# dwarfid.net
KiCad netlist of a schematic drawn in EAGLE
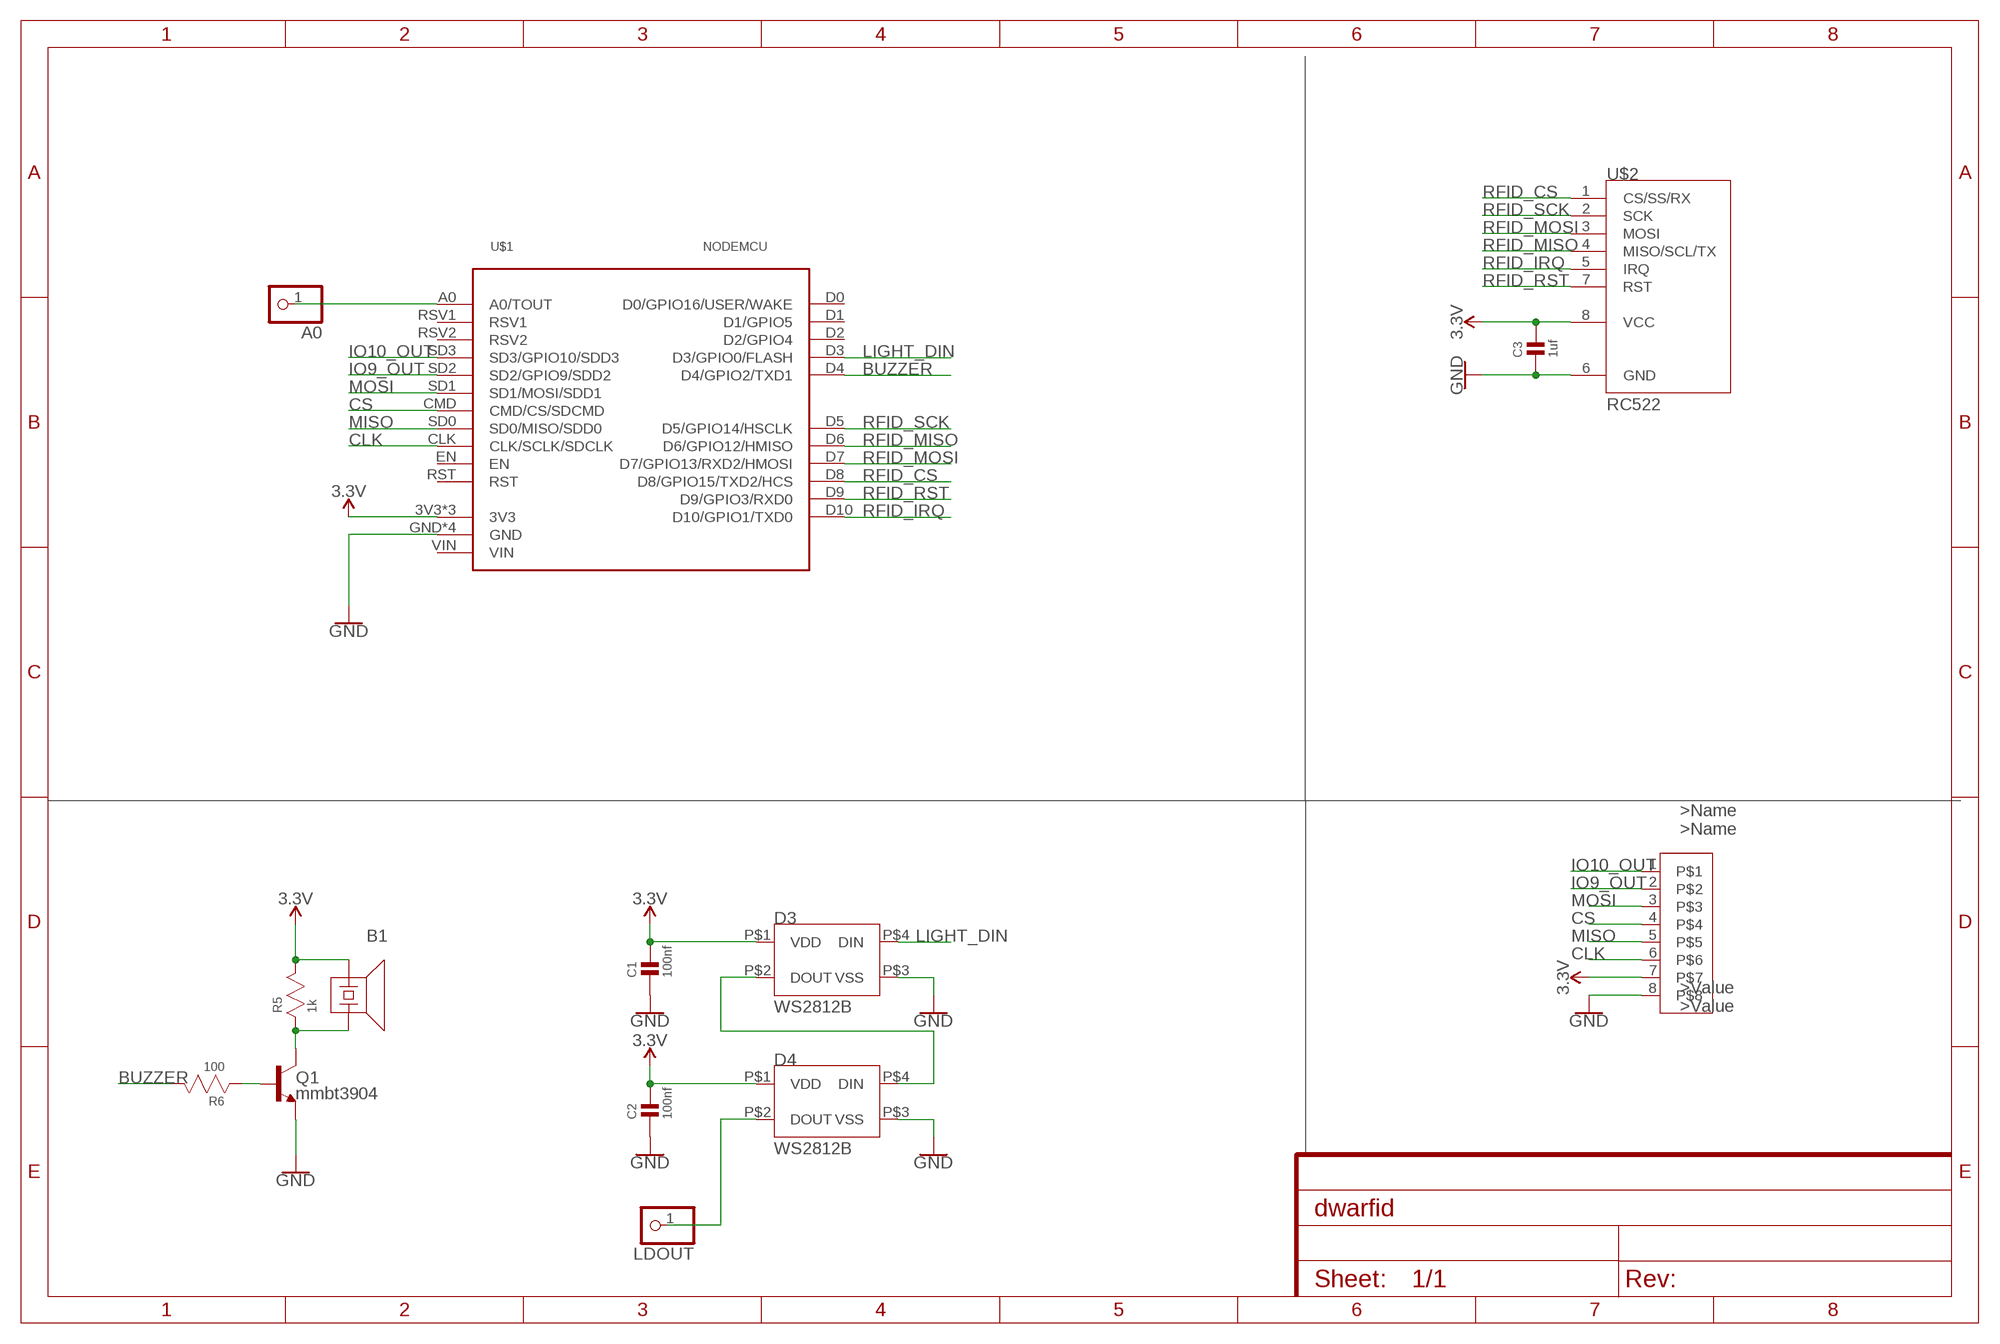
[diagram p0: schematic, sheet 1]

(export (version "E")
  (design (tool "Eeschema 10.0.6"))
  (components
    (comp (ref "A0")
      (value "PINHD-1X1")
      (footprint "eagle-import:1X01")
      (libsource (lib "eagle-import") (part "PINHD-1X1"))
    )
    (comp (ref "B1")
      (value "PS1720P02_PIEZO_BUZZER")
      (footprint "eagle-import:PS1720P02_PIEZO")
      (libsource (lib "eagle-import") (part "PS1720P02_PIEZO_BUZZER"))
    )
    (comp (ref "C1")
      (value "100nf")
      (footprint "eagle-import:PASSIVE_0603")
      (libsource (lib "eagle-import") (part "CAP_0603"))
    )
    (comp (ref "C2")
      (value "100nf")
      (footprint "eagle-import:PASSIVE_0603")
      (libsource (lib "eagle-import") (part "CAP_0603"))
    )
    (comp (ref "C3")
      (value "1uf")
      (footprint "eagle-import:PASSIVE_0603")
      (libsource (lib "eagle-import") (part "CAP_0603"))
    )
    (comp (ref "D3")
      (value "WS2812B")
      (footprint "eagle-import:WS2812B")
      (libsource (lib "eagle-import") (part "WS2812B"))
    )
    (comp (ref "D4")
      (value "WS2812B")
      (footprint "eagle-import:WS2812B")
      (libsource (lib "eagle-import") (part "WS2812B"))
    )
    (comp (ref "LDOUT")
      (value "PINHD-1X1")
      (footprint "eagle-import:1X01")
      (libsource (lib "eagle-import") (part "PINHD-1X1"))
    )
    (comp (ref "Q1")
      (value "mmbt3904")
      (footprint "eagle-import:SOT23-3")
      (libsource (lib "eagle-import") (part "TRANS_NPN-MMBT2222AL"))
    )
    (comp (ref "R5")
      (value "1k")
      (footprint "eagle-import:PASSIVE_0603")
      (libsource (lib "eagle-import") (part "RES_0603"))
    )
    (comp (ref "R6")
      (value "100")
      (footprint "eagle-import:PASSIVE_0603")
      (libsource (lib "eagle-import") (part "RES_0603"))
    )
    (comp (ref "U$1")
      (value "NODEMCU")
      (footprint "eagle-import:NODEMCU")
      (libsource (lib "eagle-import") (part "NODEMCU"))
    )
    (comp (ref "U$2")
      (value "RC522")
      (footprint "eagle-import:RC522")
      (libsource (lib "eagle-import") (part "RC522"))
    )
    (comp (ref "U$3")
      (value "JST8_2MM_RIGHTANGLE")
      (footprint "eagle-import:JST_2MM_8POS")
      (libsource (lib "eagle-import") (part "JST8_2MM_RIGHTANGLE"))
    )
  )
  (nets
    (net (code "1") (name "/BUZZER") (class "Default")
      (node (ref "R6") (pin "P$2") (pinfunction "P$2_P$2") (pintype "bidirectional"))
      (node (ref "U$1") (pin "D4") (pinfunction "D4/GPIO2/TXD1_D4") (pintype "bidirectional"))
    )
    (net (code "2") (name "/CLK") (class "Default")
      (node (ref "U$1") (pin "CLK") (pinfunction "CLK/SCLK/SDCLK_CLK") (pintype "bidirectional"))
      (node (ref "U$3") (pin "6") (pinfunction "P$6_6") (pintype "bidirectional"))
    )
    (net (code "3") (name "/CS") (class "Default")
      (node (ref "U$1") (pin "CMD") (pinfunction "CMD/CS/SDCMD_CMD") (pintype "bidirectional"))
      (node (ref "U$3") (pin "4") (pinfunction "P$4_4") (pintype "bidirectional"))
    )
    (net (code "4") (name "/IO9_OUT") (class "Default")
      (node (ref "U$1") (pin "SD2") (pinfunction "SD2/GPIO9/SDD2_SD2") (pintype "bidirectional"))
      (node (ref "U$3") (pin "2") (pinfunction "P$2_2") (pintype "bidirectional"))
    )
    (net (code "5") (name "/IO10_OUT") (class "Default")
      (node (ref "U$1") (pin "SD3") (pinfunction "SD3/GPIO10/SDD3_SD3") (pintype "bidirectional"))
      (node (ref "U$3") (pin "1") (pinfunction "P$1_1") (pintype "bidirectional"))
    )
    (net (code "6") (name "/LIGHT_DIN") (class "Default")
      (node (ref "D3") (pin "P$4") (pinfunction "DIN_P$4") (pintype "bidirectional"))
      (node (ref "U$1") (pin "D3") (pinfunction "D3/GPIO0/FLASH_D3") (pintype "bidirectional"))
    )
    (net (code "7") (name "/MISO") (class "Default")
      (node (ref "U$1") (pin "SD0") (pinfunction "SD0/MISO/SDD0_SD0") (pintype "bidirectional"))
      (node (ref "U$3") (pin "5") (pinfunction "P$5_5") (pintype "bidirectional"))
    )
    (net (code "8") (name "/MOSI") (class "Default")
      (node (ref "U$1") (pin "SD1") (pinfunction "SD1/MOSI/SDD1_SD1") (pintype "bidirectional"))
      (node (ref "U$3") (pin "3") (pinfunction "P$3_3") (pintype "bidirectional"))
    )
    (net (code "9") (name "/RFID_CS") (class "Default")
      (node (ref "U$1") (pin "D8") (pinfunction "D8/GPIO15/TXD2/HCS_D8") (pintype "bidirectional"))
      (node (ref "U$2") (pin "1") (pinfunction "CS/SS/RX_1") (pintype "bidirectional"))
    )
    (net (code "10") (name "/RFID_IRQ") (class "Default")
      (node (ref "U$1") (pin "D10") (pinfunction "D10/GPIO1/TXD0_D10") (pintype "bidirectional"))
      (node (ref "U$2") (pin "5") (pinfunction "IRQ_5") (pintype "bidirectional"))
    )
    (net (code "11") (name "/RFID_MISO") (class "Default")
      (node (ref "U$1") (pin "D6") (pinfunction "D6/GPIO12/HMISO_D6") (pintype "bidirectional"))
      (node (ref "U$2") (pin "4") (pinfunction "MISO/SCL/TX_4") (pintype "bidirectional"))
    )
    (net (code "12") (name "/RFID_MOSI") (class "Default")
      (node (ref "U$1") (pin "D7") (pinfunction "D7/GPIO13/RXD2/HMOSI_D7") (pintype "bidirectional"))
      (node (ref "U$2") (pin "3") (pinfunction "MOSI_3") (pintype "bidirectional"))
    )
    (net (code "13") (name "/RFID_RST") (class "Default")
      (node (ref "U$1") (pin "D9") (pinfunction "D9/GPIO3/RXD0_D9") (pintype "bidirectional"))
      (node (ref "U$2") (pin "7") (pinfunction "RST_7") (pintype "bidirectional"))
    )
    (net (code "14") (name "/RFID_SCK") (class "Default")
      (node (ref "U$1") (pin "D5") (pinfunction "D5/GPIO14/HSCLK_D5") (pintype "bidirectional"))
      (node (ref "U$2") (pin "2") (pinfunction "SCK_2") (pintype "bidirectional"))
    )
    (net (code "15") (name "3.3V") (class "Default")
      (node (ref "B1") (pin "P$1") (pinfunction "P$1_P$1") (pintype "bidirectional"))
      (node (ref "C1") (pin "P$2") (pinfunction "P$2_P$2") (pintype "bidirectional"))
      (node (ref "C2") (pin "P$2") (pinfunction "P$2_P$2") (pintype "bidirectional"))
      (node (ref "C3") (pin "P$2") (pinfunction "P$2_P$2") (pintype "bidirectional"))
      (node (ref "D3") (pin "P$1") (pinfunction "VDD_P$1") (pintype "bidirectional"))
      (node (ref "D4") (pin "P$1") (pinfunction "VDD_P$1") (pintype "bidirectional"))
      (node (ref "R5") (pin "P$2") (pinfunction "P$2_P$2") (pintype "bidirectional"))
      (node (ref "U$1") (pin "3V3") (pinfunction "3V3_3V3") (pintype "bidirectional"))
      (node (ref "U$1") (pin "3V3_2") (pinfunction "3V3_3V3_2") (pintype "bidirectional"))
      (node (ref "U$1") (pin "3V3_3") (pinfunction "3V3_3V3_3") (pintype "bidirectional"))
      (node (ref "U$2") (pin "8") (pinfunction "VCC_8") (pintype "bidirectional"))
      (node (ref "U$3") (pin "7") (pinfunction "P$7_7") (pintype "bidirectional"))
    )
    (net (code "16") (name "GND") (class "Default")
      (node (ref "C1") (pin "P$1") (pinfunction "P$1_P$1") (pintype "bidirectional"))
      (node (ref "C2") (pin "P$1") (pinfunction "P$1_P$1") (pintype "bidirectional"))
      (node (ref "C3") (pin "P$1") (pinfunction "P$1_P$1") (pintype "bidirectional"))
      (node (ref "D3") (pin "P$3") (pinfunction "VSS_P$3") (pintype "bidirectional"))
      (node (ref "D4") (pin "P$3") (pinfunction "VSS_P$3") (pintype "bidirectional"))
      (node (ref "Q1") (pin "2") (pinfunction "E_2") (pintype "passive"))
      (node (ref "U$1") (pin "GND") (pinfunction "GND_GND") (pintype "bidirectional"))
      (node (ref "U$1") (pin "GND2") (pinfunction "GND_GND2") (pintype "bidirectional"))
      (node (ref "U$1") (pin "GND3") (pinfunction "GND_GND3") (pintype "bidirectional"))
      (node (ref "U$1") (pin "GND4") (pinfunction "GND_GND4") (pintype "bidirectional"))
      (node (ref "U$2") (pin "6") (pinfunction "GND_6") (pintype "bidirectional"))
      (node (ref "U$3") (pin "8") (pinfunction "P$8_8") (pintype "bidirectional"))
    )
    (net (code "17") (name "Net-(D3-DOUT)") (class "Default")
      (node (ref "D3") (pin "P$2") (pinfunction "DOUT_P$2") (pintype "bidirectional"))
      (node (ref "D4") (pin "P$4") (pinfunction "DIN_P$4") (pintype "bidirectional"))
    )
    (net (code "18") (name "Net-(D4-DOUT)") (class "Default")
      (node (ref "D4") (pin "P$2") (pinfunction "DOUT_P$2") (pintype "bidirectional"))
      (node (ref "LDOUT") (pin "1") (pinfunction "1_1") (pintype "passive"))
    )
    (net (code "19") (name "Net-(Q1-B)") (class "Default")
      (node (ref "Q1") (pin "1") (pinfunction "B_1") (pintype "passive"))
      (node (ref "R6") (pin "P$1") (pinfunction "P$1_P$1") (pintype "bidirectional"))
    )
    (net (code "20") (name "Net-(Q1-C)") (class "Default")
      (node (ref "B1") (pin "P$2") (pinfunction "P$2_P$2") (pintype "bidirectional"))
      (node (ref "Q1") (pin "3") (pinfunction "C_3") (pintype "passive"))
      (node (ref "R5") (pin "P$1") (pinfunction "P$1_P$1") (pintype "bidirectional"))
    )
    (net (code "21") (name "Net-(U$1-A0{slash}TOUT)") (class "Default")
      (node (ref "A0") (pin "1") (pinfunction "1_1") (pintype "passive"))
      (node (ref "U$1") (pin "A0") (pinfunction "A0/TOUT_A0") (pintype "bidirectional"))
    )
    (net (code "22") (name "unconnected-(U$1-D0{slash}GPIO16{slash}USER{slash}WAKE-PadD0)") (class "Default")
      (node (ref "U$1") (pin "D0") (pinfunction "D0/GPIO16/USER/WAKE_D0") (pintype "bidirectional"))
    )
    (net (code "23") (name "unconnected-(U$1-D1{slash}GPIO5-PadD1)") (class "Default")
      (node (ref "U$1") (pin "D1") (pinfunction "D1/GPIO5_D1") (pintype "bidirectional"))
    )
    (net (code "24") (name "unconnected-(U$1-D2{slash}GPIO4-PadD2)") (class "Default")
      (node (ref "U$1") (pin "D2") (pinfunction "D2/GPIO4_D2") (pintype "bidirectional"))
    )
    (net (code "25") (name "unconnected-(U$1-PadEN)") (class "Default")
      (node (ref "U$1") (pin "EN") (pinfunction "EN_EN") (pintype "bidirectional"))
    )
    (net (code "26") (name "unconnected-(U$1-PadRST)") (class "Default")
      (node (ref "U$1") (pin "RST") (pinfunction "RST_RST") (pintype "bidirectional"))
    )
    (net (code "27") (name "unconnected-(U$1-PadRSV1)") (class "Default")
      (node (ref "U$1") (pin "RSV1") (pinfunction "RSV1_RSV1") (pintype "bidirectional"))
    )
    (net (code "28") (name "unconnected-(U$1-PadRSV2)") (class "Default")
      (node (ref "U$1") (pin "RSV2") (pinfunction "RSV2_RSV2") (pintype "bidirectional"))
    )
    (net (code "29") (name "unconnected-(U$1-PadVIN)") (class "Default")
      (node (ref "U$1") (pin "VIN") (pinfunction "VIN_VIN") (pintype "bidirectional"))
    )
  )
)
